# PG12_CURRENT_INTEGRATION.net
KiCad netlist of a schematic drawn in Altium Designer
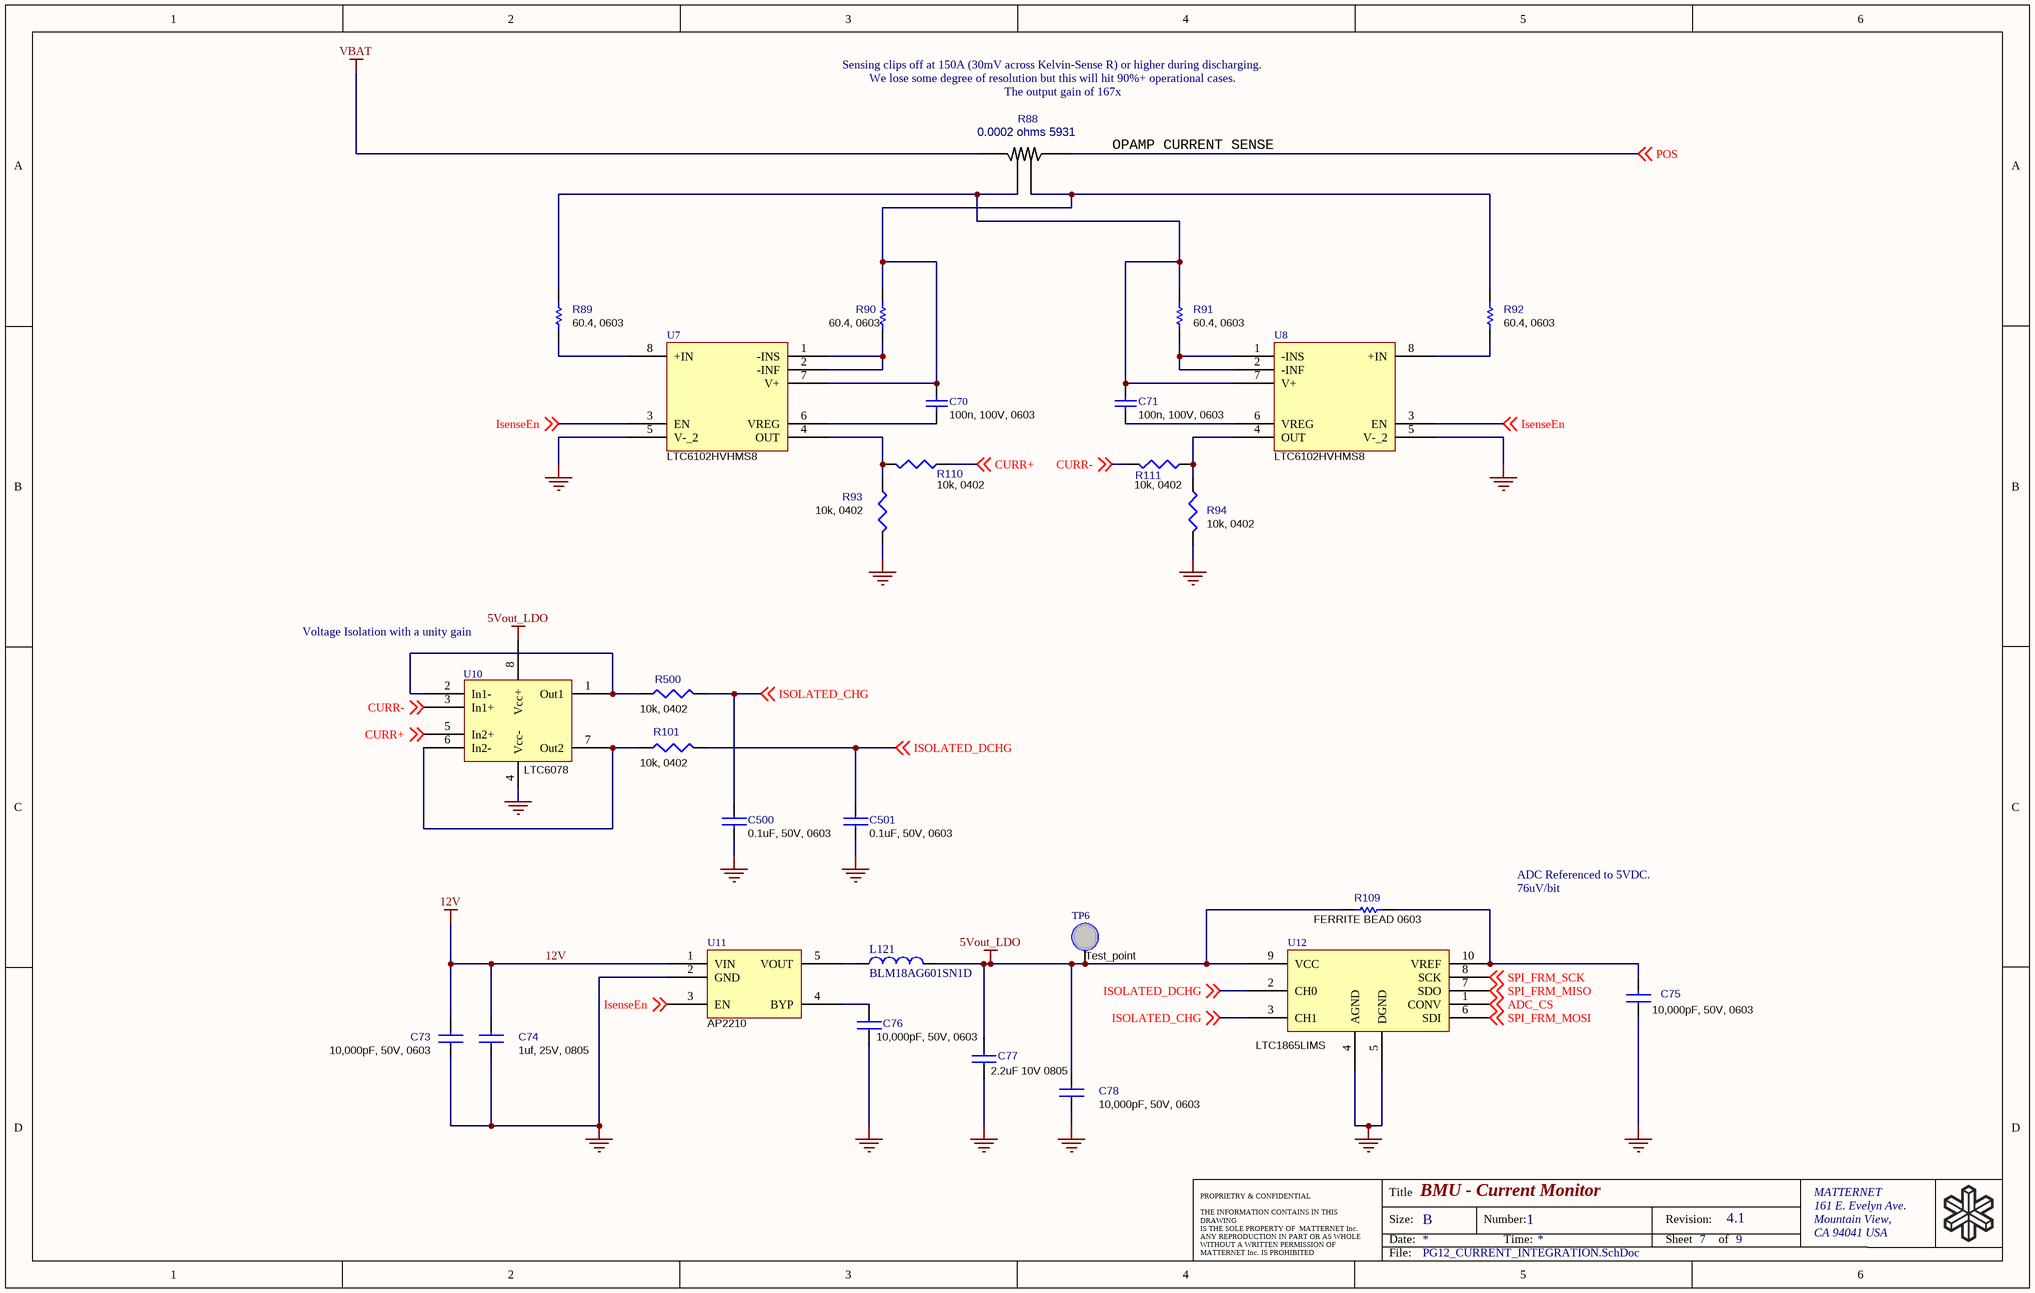
[diagram p0: PG12_CURRENT_INTEGRATION.SchDoc]

(export (version "E")
  (design (tool "Eeschema 10.0.6"))
  (components
    (comp (ref "C70")
      (value "100n, 100V, 0603")
      (footprint "C0603")
      (description "CAP CER 100n 100V X7R 0603")
      (fields
        (field (name "MANUFACTURER") "Murata")
        (field (name "MANUFACTURER PART NUMBER") "GCJ188R72A104KA01D")
      )
      (libsource (lib "Miscellaneous Devices") (part "Cap"))
    )
    (comp (ref "C71")
      (value "100n, 100V, 0603")
      (footprint "C0603")
      (description "CAP CER 100n 100V X7R 0603")
      (fields
        (field (name "MANUFACTURER") "Murata")
        (field (name "MANUFACTURER PART NUMBER") "GCJ188R72A104KA01D")
      )
      (libsource (lib "Miscellaneous Devices") (part "Cap"))
    )
    (comp (ref "C73")
      (value "10,000pF, 50V, 0603")
      (footprint "C0603")
      (description "CAP CER 10000PF 50V X7R 0603")
      (fields
        (field (name "MANUFACTURER") "TDK")
        (field (name "MANUFACTURER PART NUMBER") "CGA3E2X7R1H103K080AE")
      )
      (libsource (lib "*") (part "CAP-Generic-0603"))
    )
    (comp (ref "C74")
      (value "1uf, 25V, 0805")
      (footprint "C0805")
      (description "CAP CER 1UF 25V X7R 0805")
      (fields
        (field (name "MANUFACTURER") "Murata")
        (field (name "MANUFACTURER PART NUMBER") "GCJ21BR71E105KA12L")
      )
      (libsource (lib "*") (part "CAP-Generic-0402"))
    )
    (comp (ref "C75")
      (value "10,000pF, 50V, 0603")
      (footprint "C0603")
      (description "CAP CER 10000PF 50V X7R 0603")
      (fields
        (field (name "MANUFACTURER") "TDK")
        (field (name "MANUFACTURER PART NUMBER") "CGA3E2X7R1H103K080AE")
      )
      (libsource (lib "*") (part "CAP-Generic-0603"))
    )
    (comp (ref "C76")
      (value "10,000pF, 50V, 0603")
      (footprint "C0603")
      (description "CAP CER 10000PF 50V X7R 0603")
      (fields
        (field (name "MANUFACTURER") "TDK")
        (field (name "MANUFACTURER PART NUMBER") "CGA3E2X7R1H103K080AE")
      )
      (libsource (lib "*") (part "CAP-Generic-0603"))
    )
    (comp (ref "C77")
      (value "2.2uF 10V 0805")
      (footprint "C0805")
      (description "CAP CER 2.2UF 10V 10% X7R 0805")
      (fields
        (field (name "MANUFACTURER") "KEMET")
        (field (name "MANUFACTURER PART NUMBER") "C0805X225K8RACAUTO")
      )
      (libsource (lib "*") (part "CAP-Generic-0805"))
    )
    (comp (ref "C78")
      (value "10,000pF, 50V, 0603")
      (footprint "C0603")
      (description "CAP CER 10000PF 50V X7R 0603")
      (fields
        (field (name "MANUFACTURER") "TDK")
        (field (name "MANUFACTURER PART NUMBER") "CGA3E2X7R1H103K080AE")
      )
      (libsource (lib "*") (part "CAP-Generic-0603"))
    )
    (comp (ref "C500")
      (value "0.1uF, 50V, 0603")
      (footprint "C0603")
      (description "CAP CER 0.1UF 50V 10% X7R 0603")
      (fields
        (field (name "MANUFACTURER") "Murata")
        (field (name "MANUFACTURER PART NUMBER") "GCJ188R71E104KA12D")
      )
      (libsource (lib "*") (part "CAP-Generic-0603"))
    )
    (comp (ref "C501")
      (value "0.1uF, 50V, 0603")
      (footprint "C0603")
      (description "CAP CER 0.1UF 50V 10% X7R 0603")
      (fields
        (field (name "MANUFACTURER") "Murata")
        (field (name "MANUFACTURER PART NUMBER") "GCJ188R71E104KA12D")
      )
      (libsource (lib "*") (part "CAP-Generic-0603"))
    )
    (comp (ref "L121")
      (value "BLM18AG601SN1D")
      (footprint "INDC1608X10N")
      (description "FERRITE BEAD 600 OHM 0603 1LN")
      (libsource (lib "Altium") (part "BLM18AG601SN1D"))
    )
    (comp (ref "R88")
      (value "WSL2512R0700FEA")
      (footprint "R5931")
      (description "RES SMD 200 UOHM 1% 5W 5931")
      (fields
        (field (name "MANUFACTURER") "Vishay Dale")
        (field (name "MANUFACTURER PART NUMBER") "WSL5931L2000FEA")
      )
      (libsource (lib "RonsLib1") (part "Res_4Term"))
    )
    (comp (ref "R89")
      (value "60.4, 0603")
      (footprint "R0603")
      (description "RES SMD 60.4 OHM 1% 1/10W 0603")
      (fields
        (field (name "MANUFACTURER") "Vishay")
        (field (name "MANUFACTURER PART NUMBER") "CRCW060360R4FKEA")
        (field (name "PUBLISHER") "Altium Limited")
      )
      (libsource (lib "Miscellaneous Devices") (part "Res1"))
    )
    (comp (ref "R90")
      (value "60.4, 0603")
      (footprint "R0603")
      (description "RES SMD 60.4 OHM 1% 1/10W 0603")
      (fields
        (field (name "MANUFACTURER") "Vishay")
        (field (name "MANUFACTURER PART NUMBER") "CRCW060360R4FKEA")
        (field (name "PUBLISHER") "Altium Limited")
      )
      (libsource (lib "Miscellaneous Devices") (part "Res1"))
    )
    (comp (ref "R91")
      (value "60.4, 0603")
      (footprint "R0603")
      (description "RES SMD 60.4 OHM 1% 1/10W 0603")
      (fields
        (field (name "MANUFACTURER") "Vishay")
        (field (name "MANUFACTURER PART NUMBER") "CRCW060360R4FKEA")
        (field (name "PUBLISHER") "Altium Limited")
      )
      (libsource (lib "Miscellaneous Devices") (part "Res1"))
    )
    (comp (ref "R92")
      (value "60.4, 0603")
      (footprint "R0603")
      (description "RES SMD 60.4 OHM 1% 1/10W 0603")
      (fields
        (field (name "MANUFACTURER") "Vishay")
        (field (name "MANUFACTURER PART NUMBER") "CRCW060360R4FKEA")
        (field (name "PUBLISHER") "Altium Limited")
      )
      (libsource (lib "Miscellaneous Devices") (part "Res1"))
    )
    (comp (ref "R93")
      (value "10k, 0402")
      (footprint "R0402")
      (description "RES SMD 10K OHM 1% 1/16W 0402")
      (fields
        (field (name "MANUFACTURER") "Vishay Dale")
        (field (name "MANUFACTURER PART NUMBER") "CRCW040210K0FKTD")
      )
      (libsource (lib "Miscellaneous Devices") (part "R-Generic-0402"))
    )
    (comp (ref "R94")
      (value "10k, 0402")
      (footprint "R0402")
      (description "RES SMD 10K OHM 1% 1/16W 0402")
      (fields
        (field (name "MANUFACTURER") "Vishay Dale")
        (field (name "MANUFACTURER PART NUMBER") "CRCW040210K0FKTD")
      )
      (libsource (lib "Miscellaneous Devices") (part "R-Generic-0402"))
    )
    (comp (ref "R101")
      (value "10k, 0402")
      (footprint "R0402")
      (description "RES SMD 10K OHM 1% 1/16W 0402")
      (fields
        (field (name "MANUFACTURER") "Vishay Dale")
        (field (name "MANUFACTURER PART NUMBER") "CRCW040210K0FKTD")
      )
      (libsource (lib "Miscellaneous Devices") (part "R-Generic-0402"))
    )
    (comp (ref "R109")
      (value "FERRITE BEAD 0603")
      (footprint "R0603")
      (description "FERRITE BEAD 600 OHM 0603 1LN")
      (fields
        (field (name "MANUFACTURER") "Wurth Electronics")
        (field (name "MANUFACTURER PART NUMBER") "742792651")
      )
      (libsource (lib "Miscellaneous Devices") (part "Res1"))
    )
    (comp (ref "R110")
      (value "10k, 0402")
      (footprint "R0402")
      (description "RES SMD 10K OHM 1% 1/16W 0402")
      (fields
        (field (name "MANUFACTURER") "Vishay Dale")
        (field (name "MANUFACTURER PART NUMBER") "CRCW040210K0FKTD")
      )
      (libsource (lib "Miscellaneous Devices") (part "R-Generic-0402"))
    )
    (comp (ref "R111")
      (value "10k, 0402")
      (footprint "R0402")
      (description "RES SMD 10K OHM 1% 1/16W 0402")
      (fields
        (field (name "MANUFACTURER") "Vishay Dale")
        (field (name "MANUFACTURER PART NUMBER") "CRCW040210K0FKTD")
      )
      (libsource (lib "Miscellaneous Devices") (part "R-Generic-0402"))
    )
    (comp (ref "R500")
      (value "10k, 0402")
      (footprint "R0402")
      (description "RES SMD 10K OHM 1% 1/16W 0402")
      (fields
        (field (name "MANUFACTURER") "Vishay Dale")
        (field (name "MANUFACTURER PART NUMBER") "CRCW040210K0FKTD")
      )
      (libsource (lib "Miscellaneous Devices") (part "R-Generic-0402"))
    )
    (comp (ref "TP6")
      (value "Test_point")
      (footprint "TP")
      (libsource (lib "M2_V8_BMU_V1.0") (part "Test_point"))
    )
    (comp (ref "U7")
      (value "LTC6102HVHMS8")
      (footprint "8MSOP")
      (description "IC OPAMP CURR SENSE 200KHZ 8MSOP")
      (fields
        (field (name "MANUFACTURER") "Analog Devices / Linear Technology")
        (field (name "MANUFACTURER PART NUMBER") "LTC6102HMS8-1#PBF")
      )
      (libsource (lib "M2_V8_BMU_V1.0") (part "LTC6102HVHMS8"))
    )
    (comp (ref "U8")
      (value "LTC6102HVHMS8")
      (footprint "8MSOP")
      (description "IC OPAMP CURR SENSE 200KHZ 8MSOP")
      (fields
        (field (name "MANUFACTURER") "Analog Devices / Linear Technology")
        (field (name "MANUFACTURER PART NUMBER") "LTC6102HMS8-1#PBF")
      )
      (libsource (lib "") (part "LTC6102HVHMS8_1"))
    )
    (comp (ref "U10")
      (value "LTC6078")
      (footprint "8MSOP")
      (description "IC OPAMP GP 750KHZ RRO 8MSOP")
      (fields
        (field (name "MANUFACTURER") "Analog Devices / Linear Technology")
        (field (name "MANUFACTURER PART NUMBER") "LTC6078HMS8#TRPBF")
      )
      (libsource (lib "M2_V8_BMU_V1.0") (part "TSV912IQ2T"))
    )
    (comp (ref "U11")
      (value "AP2210")
      (footprint "SOT23-5")
      (description "IC REG LINEAR 5V 300MA SOT23-5")
      (fields (field (name "PART NUMBER") "AP2210K-5.0TRG1") (field (name "MANUFACTURER") "Diodes"))
      (libsource (lib "M2_V8_BMU_V1.0") (part "AP2210K"))
    )
    (comp (ref "U12")
      (value "LTC1865LIMS")
      (footprint "10-MSOP")
      (description "IC A/D CONV 2CH 16BIT 10-MSOP")
      (fields
        (field (name "MANUFACTURER") "Analog Devices / Linear Technology")
        (field (name "MANUFACTURER PART NUMBER") "LTC1865LIMS#PBF")
      )
      (libsource (lib "M2_V8_BMU_V1.0") (part "LTC1865"))
    )
  )
  (nets
    (net (code "1") (name "5Vout_LDO") (class "Default")
      (node (ref "C77") (pin "2") (pinfunction "2_2") (pintype "passive"))
      (node (ref "C78") (pin "2") (pinfunction "2_2") (pintype "passive"))
      (node (ref "L121") (pin "2") (pinfunction "2_2") (pintype "passive"))
      (node (ref "R109") (pin "2") (pinfunction "2_2") (pintype "passive"))
      (node (ref "TP6") (pin "1") (pinfunction "1_1") (pintype "passive"))
      (node (ref "U10") (pin "8") (pinfunction "Vcc+_8") (pintype "passive"))
      (node (ref "U12") (pin "9") (pinfunction "VCC_9") (pintype "passive"))
    )
    (net (code "2") (name "12V") (class "Default")
      (node (ref "C73") (pin "2") (pinfunction "2_2") (pintype "passive"))
      (node (ref "C74") (pin "2") (pinfunction "2_2") (pintype "passive"))
      (node (ref "U11") (pin "1") (pinfunction "VIN_1") (pintype "passive"))
    )
    (net (code "3") (name "ADC_CS") (class "Default")
      (node (ref "U12") (pin "1") (pinfunction "CONV_1") (pintype "passive"))
    )
    (net (code "4") (name "CURR+") (class "Default")
      (node (ref "R110") (pin "1") (pinfunction "1_1") (pintype "passive"))
      (node (ref "U10") (pin "5") (pinfunction "In2+_5") (pintype "passive"))
    )
    (net (code "5") (name "CURR-") (class "Default")
      (node (ref "R111") (pin "2") (pinfunction "2_2") (pintype "passive"))
      (node (ref "U10") (pin "3") (pinfunction "In1+_3") (pintype "passive"))
    )
    (net (code "6") (name "GND") (class "Default")
      (node (ref "C500") (pin "2") (pinfunction "2_2") (pintype "passive"))
      (node (ref "C501") (pin "2") (pinfunction "2_2") (pintype "passive"))
      (node (ref "C73") (pin "1") (pinfunction "1_1") (pintype "passive"))
      (node (ref "C74") (pin "1") (pinfunction "1_1") (pintype "passive"))
      (node (ref "C75") (pin "1") (pinfunction "1_1") (pintype "passive"))
      (node (ref "C76") (pin "1") (pinfunction "1_1") (pintype "passive"))
      (node (ref "C77") (pin "1") (pinfunction "1_1") (pintype "passive"))
      (node (ref "C78") (pin "1") (pinfunction "1_1") (pintype "passive"))
      (node (ref "R93") (pin "2") (pinfunction "2_2") (pintype "passive"))
      (node (ref "R94") (pin "2") (pinfunction "2_2") (pintype "passive"))
      (node (ref "U10") (pin "4") (pinfunction "Vcc-_4") (pintype "passive"))
      (node (ref "U11") (pin "2") (pinfunction "GND_2") (pintype "passive"))
      (node (ref "U12") (pin "4") (pinfunction "AGND_4") (pintype "passive"))
      (node (ref "U12") (pin "5") (pinfunction "DGND_5") (pintype "passive"))
      (node (ref "U7") (pin "5") (pinfunction "V-_2_5") (pintype "passive"))
      (node (ref "U8") (pin "5") (pinfunction "V-_2_5") (pintype "passive"))
    )
    (net (code "7") (name "ISOLATED_CHG") (class "Default")
      (node (ref "C500") (pin "1") (pinfunction "1_1") (pintype "passive"))
      (node (ref "R500") (pin "2") (pinfunction "2_2") (pintype "passive"))
      (node (ref "U12") (pin "3") (pinfunction "CH1_3") (pintype "passive"))
    )
    (net (code "8") (name "ISOLATED_DCHG") (class "Default")
      (node (ref "C501") (pin "1") (pinfunction "1_1") (pintype "passive"))
      (node (ref "R101") (pin "2") (pinfunction "2_2") (pintype "passive"))
      (node (ref "U12") (pin "2") (pinfunction "CH0_2") (pintype "passive"))
    )
    (net (code "9") (name "IsenseEn") (class "Default")
      (node (ref "U11") (pin "3") (pinfunction "EN_3") (pintype "passive"))
      (node (ref "U7") (pin "3") (pinfunction "EN_3") (pintype "passive"))
      (node (ref "U8") (pin "3") (pinfunction "EN_3") (pintype "passive"))
    )
    (net (code "10") (name "Net-(U7-+IN)") (class "Default")
      (node (ref "R89") (pin "1") (pinfunction "1_1") (pintype "passive"))
      (node (ref "U7") (pin "8") (pinfunction "+IN_8") (pintype "passive"))
    )
    (net (code "11") (name "Net-(U7--INF)") (class "Default")
      (node (ref "R90") (pin "1") (pinfunction "1_1") (pintype "passive"))
      (node (ref "U7") (pin "1") (pinfunction "-INS_1") (pintype "passive"))
      (node (ref "U7") (pin "2") (pinfunction "-INF_2") (pintype "passive"))
    )
    (net (code "12") (name "Net-(U7-OUT)") (class "Default")
      (node (ref "R110") (pin "2") (pinfunction "2_2") (pintype "passive"))
      (node (ref "R93") (pin "1") (pinfunction "1_1") (pintype "passive"))
      (node (ref "U7") (pin "4") (pinfunction "OUT_4") (pintype "passive"))
    )
    (net (code "13") (name "Net-(U7-V+)") (class "Default")
      (node (ref "C70") (pin "2") (pinfunction "2_2") (pintype "passive"))
      (node (ref "R88") (pin "4") (pinfunction "4_4") (pintype "passive"))
      (node (ref "R90") (pin "2") (pinfunction "2_2") (pintype "passive"))
      (node (ref "R92") (pin "2") (pinfunction "2_2") (pintype "passive"))
      (node (ref "U7") (pin "7") (pinfunction "V+_7") (pintype "passive"))
    )
    (net (code "14") (name "Net-(U7-VREG)") (class "Default")
      (node (ref "C70") (pin "1") (pinfunction "1_1") (pintype "passive"))
      (node (ref "U7") (pin "6") (pinfunction "VREG_6") (pintype "passive"))
    )
    (net (code "15") (name "Net-(U8-+IN)") (class "Default")
      (node (ref "R92") (pin "1") (pinfunction "1_1") (pintype "passive"))
      (node (ref "U8") (pin "8") (pinfunction "+IN_8") (pintype "passive"))
    )
    (net (code "16") (name "Net-(U8--INF)") (class "Default")
      (node (ref "R91") (pin "1") (pinfunction "1_1") (pintype "passive"))
      (node (ref "U8") (pin "1") (pinfunction "-INS_1") (pintype "passive"))
      (node (ref "U8") (pin "2") (pinfunction "-INF_2") (pintype "passive"))
    )
    (net (code "17") (name "Net-(U8-OUT)") (class "Default")
      (node (ref "R111") (pin "1") (pinfunction "1_1") (pintype "passive"))
      (node (ref "R94") (pin "1") (pinfunction "1_1") (pintype "passive"))
      (node (ref "U8") (pin "4") (pinfunction "OUT_4") (pintype "passive"))
    )
    (net (code "18") (name "Net-(U8-V+)") (class "Default")
      (node (ref "C71") (pin "2") (pinfunction "2_2") (pintype "passive"))
      (node (ref "R88") (pin "3") (pinfunction "3_3") (pintype "passive"))
      (node (ref "R89") (pin "2") (pinfunction "2_2") (pintype "passive"))
      (node (ref "R91") (pin "2") (pinfunction "2_2") (pintype "passive"))
      (node (ref "U8") (pin "7") (pinfunction "V+_7") (pintype "passive"))
    )
    (net (code "19") (name "Net-(U8-VREG)") (class "Default")
      (node (ref "C71") (pin "1") (pinfunction "1_1") (pintype "passive"))
      (node (ref "U8") (pin "6") (pinfunction "VREG_6") (pintype "passive"))
    )
    (net (code "20") (name "Net-(U10-In1-)") (class "Default")
      (node (ref "R500") (pin "1") (pinfunction "1_1") (pintype "passive"))
      (node (ref "U10") (pin "1") (pinfunction "Out1_1") (pintype "passive"))
      (node (ref "U10") (pin "2") (pinfunction "In1-_2") (pintype "passive"))
    )
    (net (code "21") (name "Net-(U10-In2-)") (class "Default")
      (node (ref "R101") (pin "1") (pinfunction "1_1") (pintype "passive"))
      (node (ref "U10") (pin "6") (pinfunction "In2-_6") (pintype "passive"))
      (node (ref "U10") (pin "7") (pinfunction "Out2_7") (pintype "passive"))
    )
    (net (code "22") (name "Net-(U11-BYP)") (class "Default")
      (node (ref "C76") (pin "2") (pinfunction "2_2") (pintype "passive"))
      (node (ref "U11") (pin "4") (pinfunction "BYP_4") (pintype "passive"))
    )
    (net (code "23") (name "Net-(U11-VOUT)") (class "Default")
      (node (ref "L121") (pin "1") (pinfunction "1_1") (pintype "passive"))
      (node (ref "U11") (pin "5") (pinfunction "VOUT_5") (pintype "passive"))
    )
    (net (code "24") (name "Net-(U12-VREF)") (class "Default")
      (node (ref "C75") (pin "2") (pinfunction "2_2") (pintype "passive"))
      (node (ref "R109") (pin "1") (pinfunction "1_1") (pintype "passive"))
      (node (ref "U12") (pin "10") (pinfunction "VREF_10") (pintype "passive"))
    )
    (net (code "25") (name "POS") (class "Default")
      (node (ref "R88") (pin "2") (pinfunction "2_2") (pintype "passive"))
    )
    (net (code "26") (name "SPI_FRM_MISO") (class "Default")
      (node (ref "U12") (pin "7") (pinfunction "SDO_7") (pintype "passive"))
    )
    (net (code "27") (name "SPI_FRM_MOSI") (class "Default")
      (node (ref "U12") (pin "6") (pinfunction "SDI_6") (pintype "passive"))
    )
    (net (code "28") (name "SPI_FRM_SCK") (class "Default")
      (node (ref "U12") (pin "8") (pinfunction "SCK_8") (pintype "passive"))
    )
    (net (code "29") (name "VBAT") (class "Default")
      (node (ref "R88") (pin "1") (pinfunction "1_1") (pintype "passive"))
    )
  )
)
